# Sheet4.net
KiCad netlist of a schematic drawn in Altium Designer
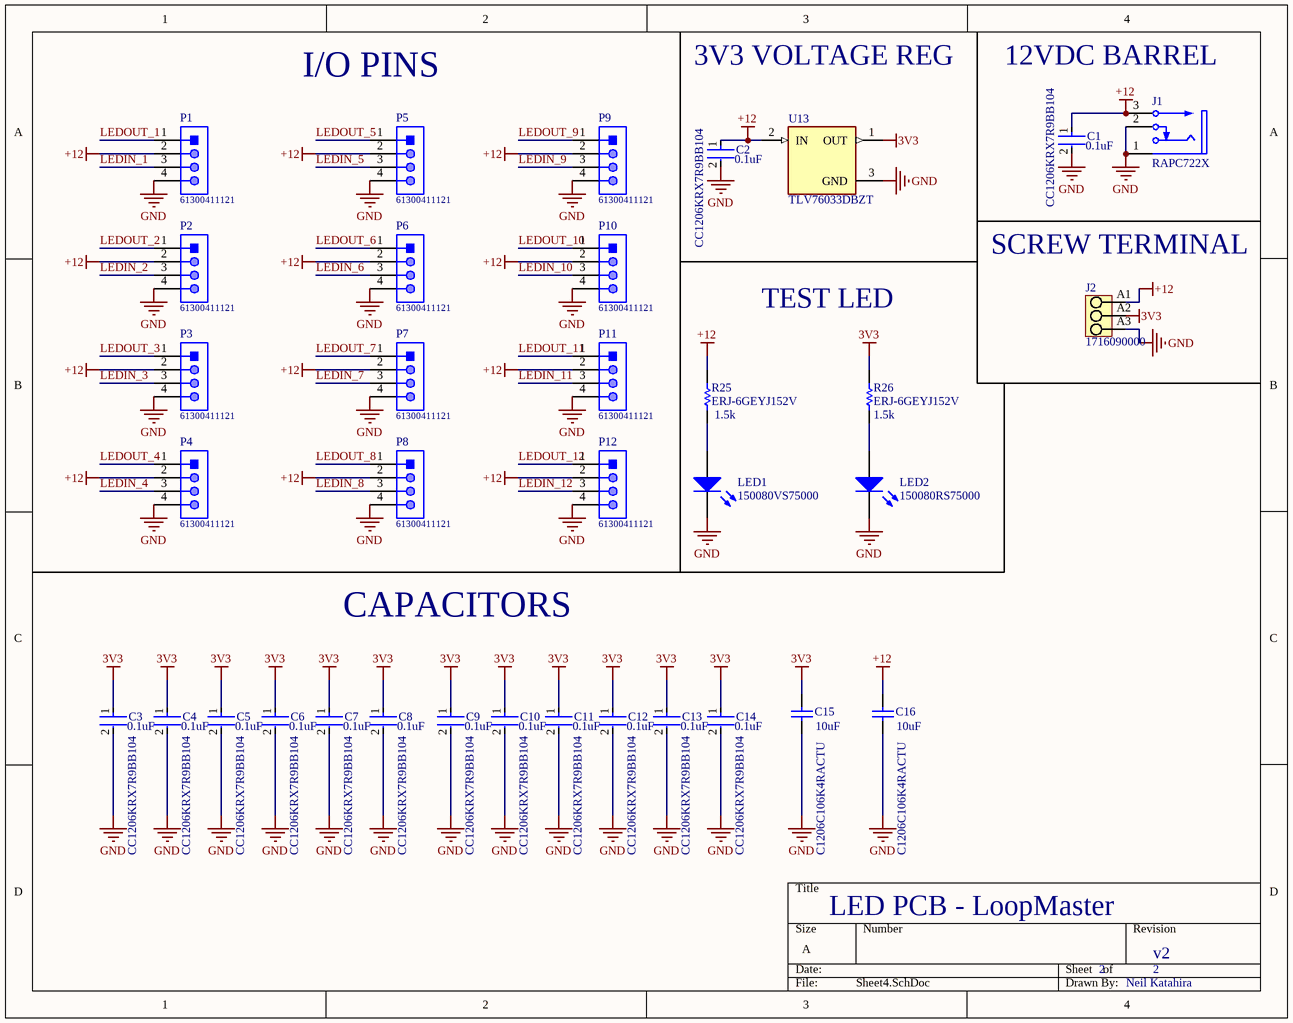
[diagram p0: Sheet4.SchDoc]

(export (version "E")
  (design (tool "Eeschema 10.0.6"))
  (components
    (comp (ref "C1")
      (value "CC1206KRX7R9BB104")
      (footprint "FP-CC1206-1_25-MFG")
      (description "CAP CER 0.1UF 50V X7R 1206")
      (fields
        (field (name "OCTOPART") "https://octopart.com/cc1206krx7r9bb104-yageo-39467816")
        (field (name "TOLERANCE") "0.1")
      )
      (libsource (lib "Altium Content Vault") (part "11868f565c42a9108669ba33697ecf6"))
    )
    (comp (ref "C2")
      (value "CC1206KRX7R9BB104")
      (footprint "FP-CC1206-1_25-MFG")
      (description "CAP CER 0.1UF 50V X7R 1206")
      (fields
        (field (name "OCTOPART") "https://octopart.com/cc1206krx7r9bb104-yageo-39467816")
        (field (name "TOLERANCE") "0.1")
      )
      (libsource (lib "Altium Content Vault") (part "11868f565c42a9108669ba33697ecf6"))
    )
    (comp (ref "C3")
      (value "CC1206KRX7R9BB104")
      (footprint "FP-CC1206-1_25-MFG")
      (description "CAP CER 0.1UF 50V X7R 1206")
      (fields
        (field (name "OCTOPART") "https://octopart.com/cc1206krx7r9bb104-yageo-39467816")
        (field (name "TOLERANCE") "0.1")
      )
      (libsource (lib "Altium Content Vault") (part "11868f565c42a9108669ba33697ecf6"))
    )
    (comp (ref "C4")
      (value "CC1206KRX7R9BB104")
      (footprint "FP-CC1206-1_25-MFG")
      (description "CAP CER 0.1UF 50V X7R 1206")
      (fields
        (field (name "OCTOPART") "https://octopart.com/cc1206krx7r9bb104-yageo-39467816")
        (field (name "TOLERANCE") "0.1")
      )
      (libsource (lib "Altium Content Vault") (part "11868f565c42a9108669ba33697ecf6"))
    )
    (comp (ref "C5")
      (value "CC1206KRX7R9BB104")
      (footprint "FP-CC1206-1_25-MFG")
      (description "CAP CER 0.1UF 50V X7R 1206")
      (fields
        (field (name "OCTOPART") "https://octopart.com/cc1206krx7r9bb104-yageo-39467816")
        (field (name "TOLERANCE") "0.1")
      )
      (libsource (lib "Altium Content Vault") (part "11868f565c42a9108669ba33697ecf6"))
    )
    (comp (ref "C6")
      (value "CC1206KRX7R9BB104")
      (footprint "FP-CC1206-1_25-MFG")
      (description "CAP CER 0.1UF 50V X7R 1206")
      (fields
        (field (name "OCTOPART") "https://octopart.com/cc1206krx7r9bb104-yageo-39467816")
        (field (name "TOLERANCE") "0.1")
      )
      (libsource (lib "Altium Content Vault") (part "11868f565c42a9108669ba33697ecf6"))
    )
    (comp (ref "C7")
      (value "CC1206KRX7R9BB104")
      (footprint "FP-CC1206-1_25-MFG")
      (description "CAP CER 0.1UF 50V X7R 1206")
      (fields
        (field (name "OCTOPART") "https://octopart.com/cc1206krx7r9bb104-yageo-39467816")
        (field (name "TOLERANCE") "0.1")
      )
      (libsource (lib "Altium Content Vault") (part "11868f565c42a9108669ba33697ecf6"))
    )
    (comp (ref "C8")
      (value "CC1206KRX7R9BB104")
      (footprint "FP-CC1206-1_25-MFG")
      (description "CAP CER 0.1UF 50V X7R 1206")
      (fields
        (field (name "OCTOPART") "https://octopart.com/cc1206krx7r9bb104-yageo-39467816")
        (field (name "TOLERANCE") "0.1")
      )
      (libsource (lib "Altium Content Vault") (part "11868f565c42a9108669ba33697ecf6"))
    )
    (comp (ref "C9")
      (value "CC1206KRX7R9BB104")
      (footprint "FP-CC1206-1_25-MFG")
      (description "CAP CER 0.1UF 50V X7R 1206")
      (fields
        (field (name "OCTOPART") "https://octopart.com/cc1206krx7r9bb104-yageo-39467816")
        (field (name "TOLERANCE") "0.1")
      )
      (libsource (lib "Altium Content Vault") (part "11868f565c42a9108669ba33697ecf6"))
    )
    (comp (ref "C10")
      (value "CC1206KRX7R9BB104")
      (footprint "FP-CC1206-1_25-MFG")
      (description "CAP CER 0.1UF 50V X7R 1206")
      (fields
        (field (name "OCTOPART") "https://octopart.com/cc1206krx7r9bb104-yageo-39467816")
        (field (name "TOLERANCE") "0.1")
      )
      (libsource (lib "Altium Content Vault") (part "11868f565c42a9108669ba33697ecf6"))
    )
    (comp (ref "C11")
      (value "CC1206KRX7R9BB104")
      (footprint "FP-CC1206-1_25-MFG")
      (description "CAP CER 0.1UF 50V X7R 1206")
      (fields
        (field (name "OCTOPART") "https://octopart.com/cc1206krx7r9bb104-yageo-39467816")
        (field (name "TOLERANCE") "0.1")
      )
      (libsource (lib "Altium Content Vault") (part "11868f565c42a9108669ba33697ecf6"))
    )
    (comp (ref "C12")
      (value "CC1206KRX7R9BB104")
      (footprint "FP-CC1206-1_25-MFG")
      (description "CAP CER 0.1UF 50V X7R 1206")
      (fields
        (field (name "OCTOPART") "https://octopart.com/cc1206krx7r9bb104-yageo-39467816")
        (field (name "TOLERANCE") "0.1")
      )
      (libsource (lib "Altium Content Vault") (part "11868f565c42a9108669ba33697ecf6"))
    )
    (comp (ref "C13")
      (value "CC1206KRX7R9BB104")
      (footprint "FP-CC1206-1_25-MFG")
      (description "CAP CER 0.1UF 50V X7R 1206")
      (fields
        (field (name "OCTOPART") "https://octopart.com/cc1206krx7r9bb104-yageo-39467816")
        (field (name "TOLERANCE") "0.1")
      )
      (libsource (lib "Altium Content Vault") (part "11868f565c42a9108669ba33697ecf6"))
    )
    (comp (ref "C14")
      (value "CC1206KRX7R9BB104")
      (footprint "FP-CC1206-1_25-MFG")
      (description "CAP CER 0.1UF 50V X7R 1206")
      (fields
        (field (name "OCTOPART") "https://octopart.com/cc1206krx7r9bb104-yageo-39467816")
        (field (name "TOLERANCE") "0.1")
      )
      (libsource (lib "Altium Content Vault") (part "11868f565c42a9108669ba33697ecf6"))
    )
    (comp (ref "C15")
      (value "C1206C106K4RACTU")
      (footprint "CAPC3216X180X50ML20T25")
      (description "CAP, Ceramic, 10 uF, +/- 10%, 16 V, -55 to 125 degC, 1206 (3216 Metric), RoHS, Tape and Reel")
      (fields (field (name "TOLERANCE") "5%"))
      (libsource (lib "Altium Content Vault") (part "CAP-NP-2"))
    )
    (comp (ref "C16")
      (value "C1206C106K4RACTU")
      (footprint "CAPC3216X180X50ML20T25")
      (description "CAP, Ceramic, 10 uF, +/- 10%, 16 V, -55 to 125 degC, 1206 (3216 Metric), RoHS, Tape and Reel")
      (fields (field (name "TOLERANCE") "5%"))
      (libsource (lib "Altium Content Vault") (part "CAP-NP-2"))
    )
    (comp (ref "J1")
      (value "RAPC722X")
      (footprint "SWITCH-RAPC712X-3_V")
      (description "Power Jack, 5 A, 3-Pin THD, RoHS, Bulk")
      (fields (field (name "MANUFACTURER") "Switchcraft"))
      (libsource (lib "Altium Content Vault") (part "SWITCH-RAPC712X-3"))
    )
    (comp (ref "J2")
      (value "1716090000")
      (footprint "LM_5_08_90_03")
      (description "OMNIMATE Signal - series LM")
      (fields (field (name "MANUFACTURER") "Weidmueller"))
      (libsource (lib "Altium Content Vault") (part "Terminal_03_1x03"))
    )
    (comp (ref "LED1")
      (value "150080VS75000")
      (footprint "0805_A")
      (description "SMD mono-color Chip LED, WL-SMCW, Bright Green")
      (fields (field (name "MANUFACTURER") "Wuerth Elektronik"))
      (libsource (lib "Altium Content Vault") (part "WE-LED_K1A2-2"))
    )
    (comp (ref "LED2")
      (value "150080RS75000")
      (footprint "0805_A")
      (description "SMD mono-color Chip LED, WL-SMCW, Red")
      (fields (field (name "MANUFACTURER") "Wuerth Elektronik"))
      (libsource (lib "Altium Content Vault") (part "WE-LED_K1A2-2"))
    )
    (comp (ref "P1")
      (value "61300411121")
      (footprint "61300411121")
      (description "THT Vertical Pin Header WR-PHD, Pitch 2.54 mm, Single Row, 4 pins")
      (fields (field (name "MANUFACTURER") "Wurth Elektronik") (field (name "PUBLISHER") "WurthElektronik"))
      (libsource (lib "Altium Content Vault") (part "WE-CN-1P-M-R4"))
    )
    (comp (ref "P2")
      (value "61300411121")
      (footprint "61300411121")
      (description "THT Vertical Pin Header WR-PHD, Pitch 2.54 mm, Single Row, 4 pins")
      (fields (field (name "MANUFACTURER") "Wurth Elektronik") (field (name "PUBLISHER") "WurthElektronik"))
      (libsource (lib "Altium Content Vault") (part "WE-CN-1P-M-R4"))
    )
    (comp (ref "P3")
      (value "61300411121")
      (footprint "61300411121")
      (description "THT Vertical Pin Header WR-PHD, Pitch 2.54 mm, Single Row, 4 pins")
      (fields (field (name "MANUFACTURER") "Wurth Elektronik") (field (name "PUBLISHER") "WurthElektronik"))
      (libsource (lib "Altium Content Vault") (part "WE-CN-1P-M-R4"))
    )
    (comp (ref "P4")
      (value "61300411121")
      (footprint "61300411121")
      (description "THT Vertical Pin Header WR-PHD, Pitch 2.54 mm, Single Row, 4 pins")
      (fields (field (name "MANUFACTURER") "Wurth Elektronik") (field (name "PUBLISHER") "WurthElektronik"))
      (libsource (lib "Altium Content Vault") (part "WE-CN-1P-M-R4"))
    )
    (comp (ref "P5")
      (value "61300411121")
      (footprint "61300411121")
      (description "THT Vertical Pin Header WR-PHD, Pitch 2.54 mm, Single Row, 4 pins")
      (fields (field (name "MANUFACTURER") "Wurth Elektronik") (field (name "PUBLISHER") "WurthElektronik"))
      (libsource (lib "Altium Content Vault") (part "WE-CN-1P-M-R4"))
    )
    (comp (ref "P6")
      (value "61300411121")
      (footprint "61300411121")
      (description "THT Vertical Pin Header WR-PHD, Pitch 2.54 mm, Single Row, 4 pins")
      (fields (field (name "MANUFACTURER") "Wurth Elektronik") (field (name "PUBLISHER") "WurthElektronik"))
      (libsource (lib "Altium Content Vault") (part "WE-CN-1P-M-R4"))
    )
    (comp (ref "P7")
      (value "61300411121")
      (footprint "61300411121")
      (description "THT Vertical Pin Header WR-PHD, Pitch 2.54 mm, Single Row, 4 pins")
      (fields (field (name "MANUFACTURER") "Wurth Elektronik") (field (name "PUBLISHER") "WurthElektronik"))
      (libsource (lib "Altium Content Vault") (part "WE-CN-1P-M-R4"))
    )
    (comp (ref "P8")
      (value "61300411121")
      (footprint "61300411121")
      (description "THT Vertical Pin Header WR-PHD, Pitch 2.54 mm, Single Row, 4 pins")
      (fields (field (name "MANUFACTURER") "Wurth Elektronik") (field (name "PUBLISHER") "WurthElektronik"))
      (libsource (lib "Altium Content Vault") (part "WE-CN-1P-M-R4"))
    )
    (comp (ref "P9")
      (value "61300411121")
      (footprint "61300411121")
      (description "THT Vertical Pin Header WR-PHD, Pitch 2.54 mm, Single Row, 4 pins")
      (fields (field (name "MANUFACTURER") "Wurth Elektronik") (field (name "PUBLISHER") "WurthElektronik"))
      (libsource (lib "Altium Content Vault") (part "WE-CN-1P-M-R4"))
    )
    (comp (ref "P10")
      (value "61300411121")
      (footprint "61300411121")
      (description "THT Vertical Pin Header WR-PHD, Pitch 2.54 mm, Single Row, 4 pins")
      (fields (field (name "MANUFACTURER") "Wurth Elektronik") (field (name "PUBLISHER") "WurthElektronik"))
      (libsource (lib "Altium Content Vault") (part "WE-CN-1P-M-R4"))
    )
    (comp (ref "P11")
      (value "61300411121")
      (footprint "61300411121")
      (description "THT Vertical Pin Header WR-PHD, Pitch 2.54 mm, Single Row, 4 pins")
      (fields (field (name "MANUFACTURER") "Wurth Elektronik") (field (name "PUBLISHER") "WurthElektronik"))
      (libsource (lib "Altium Content Vault") (part "WE-CN-1P-M-R4"))
    )
    (comp (ref "P12")
      (value "61300411121")
      (footprint "61300411121")
      (description "THT Vertical Pin Header WR-PHD, Pitch 2.54 mm, Single Row, 4 pins")
      (fields (field (name "MANUFACTURER") "Wurth Elektronik") (field (name "PUBLISHER") "WurthElektronik"))
      (libsource (lib "Altium Content Vault") (part "WE-CN-1P-M-R4"))
    )
    (comp (ref "R25")
      (value "ERJ-6GEYJ152V")
      (footprint "RESC2013X70X40NL20T20")
      (fields (field (name "MANUFACTURER") "Panasonic"))
      (libsource (lib "Altium Content Vault") (part "RES"))
    )
    (comp (ref "R26")
      (value "ERJ-6GEYJ152V")
      (footprint "RESC2013X70X40NL20T20")
      (fields (field (name "MANUFACTURER") "Panasonic"))
      (libsource (lib "Altium Content Vault") (part "RES"))
    )
    (comp (ref "U13")
      (value "TLV76033DBZT")
      (footprint "FP-DBZ0003A-MFG")
      (description "IC REG LINEAR 3.3V 100MA SOT23-3")
      (fields
        (field (name "MANUFACTURER") "Texas Instruments")
        (field (name "OCTOPART") "https://octopart.com/tlv76033dbzt-texas+instruments-84619834")
      )
      (libsource (lib "Altium Content Vault") (part "a333afa03112605246d85a120c5baff"))
    )
  )
  (nets
    (net (code "1") (name "+12") (class "Default")
      (node (ref "C1") (pin "1") (pinfunction "1_1") (pintype "passive"))
      (node (ref "C16") (pin "2") (pinfunction "2_2") (pintype "passive"))
      (node (ref "C2") (pin "1") (pinfunction "1_1") (pintype "passive"))
      (node (ref "J1") (pin "3") (pinfunction "3_3") (pintype "passive"))
      (node (ref "J2") (pin "A1") (pinfunction "A1_A1") (pintype "passive"))
      (node (ref "P1") (pin "2") (pinfunction "2_2") (pintype "passive"))
      (node (ref "P10") (pin "2") (pinfunction "2_2") (pintype "passive"))
      (node (ref "P11") (pin "2") (pinfunction "2_2") (pintype "passive"))
      (node (ref "P12") (pin "2") (pinfunction "2_2") (pintype "passive"))
      (node (ref "P2") (pin "2") (pinfunction "2_2") (pintype "passive"))
      (node (ref "P3") (pin "2") (pinfunction "2_2") (pintype "passive"))
      (node (ref "P4") (pin "2") (pinfunction "2_2") (pintype "passive"))
      (node (ref "P5") (pin "2") (pinfunction "2_2") (pintype "passive"))
      (node (ref "P6") (pin "2") (pinfunction "2_2") (pintype "passive"))
      (node (ref "P7") (pin "2") (pinfunction "2_2") (pintype "passive"))
      (node (ref "P8") (pin "2") (pinfunction "2_2") (pintype "passive"))
      (node (ref "P9") (pin "2") (pinfunction "2_2") (pintype "passive"))
      (node (ref "R25") (pin "2") (pinfunction "2_2") (pintype "passive"))
      (node (ref "U13") (pin "2") (pinfunction "IN_2") (pintype "input"))
    )
    (net (code "2") (name "/LEDIN_1") (class "Default")
      (node (ref "P1") (pin "3") (pinfunction "3_3") (pintype "passive"))
    )
    (net (code "3") (name "/LEDIN_2") (class "Default")
      (node (ref "P2") (pin "3") (pinfunction "3_3") (pintype "passive"))
    )
    (net (code "4") (name "/LEDIN_3") (class "Default")
      (node (ref "P3") (pin "3") (pinfunction "3_3") (pintype "passive"))
    )
    (net (code "5") (name "/LEDIN_4") (class "Default")
      (node (ref "P4") (pin "3") (pinfunction "3_3") (pintype "passive"))
    )
    (net (code "6") (name "/LEDIN_5") (class "Default")
      (node (ref "P5") (pin "3") (pinfunction "3_3") (pintype "passive"))
    )
    (net (code "7") (name "/LEDIN_6") (class "Default")
      (node (ref "P6") (pin "3") (pinfunction "3_3") (pintype "passive"))
    )
    (net (code "8") (name "/LEDIN_7") (class "Default")
      (node (ref "P7") (pin "3") (pinfunction "3_3") (pintype "passive"))
    )
    (net (code "9") (name "/LEDIN_8") (class "Default")
      (node (ref "P8") (pin "3") (pinfunction "3_3") (pintype "passive"))
    )
    (net (code "10") (name "/LEDIN_9") (class "Default")
      (node (ref "P9") (pin "3") (pinfunction "3_3") (pintype "passive"))
    )
    (net (code "11") (name "/LEDIN_10") (class "Default")
      (node (ref "P10") (pin "3") (pinfunction "3_3") (pintype "passive"))
    )
    (net (code "12") (name "/LEDIN_11") (class "Default")
      (node (ref "P11") (pin "3") (pinfunction "3_3") (pintype "passive"))
    )
    (net (code "13") (name "/LEDIN_12") (class "Default")
      (node (ref "P12") (pin "3") (pinfunction "3_3") (pintype "passive"))
    )
    (net (code "14") (name "/LEDOUT_1") (class "Default")
      (node (ref "P1") (pin "1") (pinfunction "1_1") (pintype "passive"))
    )
    (net (code "15") (name "/LEDOUT_2") (class "Default")
      (node (ref "P2") (pin "1") (pinfunction "1_1") (pintype "passive"))
    )
    (net (code "16") (name "/LEDOUT_3") (class "Default")
      (node (ref "P3") (pin "1") (pinfunction "1_1") (pintype "passive"))
    )
    (net (code "17") (name "/LEDOUT_4") (class "Default")
      (node (ref "P4") (pin "1") (pinfunction "1_1") (pintype "passive"))
    )
    (net (code "18") (name "/LEDOUT_5") (class "Default")
      (node (ref "P5") (pin "1") (pinfunction "1_1") (pintype "passive"))
    )
    (net (code "19") (name "/LEDOUT_6") (class "Default")
      (node (ref "P6") (pin "1") (pinfunction "1_1") (pintype "passive"))
    )
    (net (code "20") (name "/LEDOUT_7") (class "Default")
      (node (ref "P7") (pin "1") (pinfunction "1_1") (pintype "passive"))
    )
    (net (code "21") (name "/LEDOUT_8") (class "Default")
      (node (ref "P8") (pin "1") (pinfunction "1_1") (pintype "passive"))
    )
    (net (code "22") (name "/LEDOUT_9") (class "Default")
      (node (ref "P9") (pin "1") (pinfunction "1_1") (pintype "passive"))
    )
    (net (code "23") (name "/LEDOUT_10") (class "Default")
      (node (ref "P10") (pin "1") (pinfunction "1_1") (pintype "passive"))
    )
    (net (code "24") (name "/LEDOUT_11") (class "Default")
      (node (ref "P11") (pin "1") (pinfunction "1_1") (pintype "passive"))
    )
    (net (code "25") (name "/LEDOUT_12") (class "Default")
      (node (ref "P12") (pin "1") (pinfunction "1_1") (pintype "passive"))
    )
    (net (code "26") (name "3V3") (class "Default")
      (node (ref "C10") (pin "1") (pinfunction "1_1") (pintype "passive"))
      (node (ref "C11") (pin "1") (pinfunction "1_1") (pintype "passive"))
      (node (ref "C12") (pin "1") (pinfunction "1_1") (pintype "passive"))
      (node (ref "C13") (pin "1") (pinfunction "1_1") (pintype "passive"))
      (node (ref "C14") (pin "1") (pinfunction "1_1") (pintype "passive"))
      (node (ref "C15") (pin "2") (pinfunction "2_2") (pintype "passive"))
      (node (ref "C3") (pin "1") (pinfunction "1_1") (pintype "passive"))
      (node (ref "C4") (pin "1") (pinfunction "1_1") (pintype "passive"))
      (node (ref "C5") (pin "1") (pinfunction "1_1") (pintype "passive"))
      (node (ref "C6") (pin "1") (pinfunction "1_1") (pintype "passive"))
      (node (ref "C7") (pin "1") (pinfunction "1_1") (pintype "passive"))
      (node (ref "C8") (pin "1") (pinfunction "1_1") (pintype "passive"))
      (node (ref "C9") (pin "1") (pinfunction "1_1") (pintype "passive"))
      (node (ref "J2") (pin "A2") (pinfunction "A2_A2") (pintype "passive"))
      (node (ref "R26") (pin "2") (pinfunction "2_2") (pintype "passive"))
      (node (ref "U13") (pin "1") (pinfunction "OUT_1") (pintype "output"))
    )
    (net (code "27") (name "GND") (class "Default")
      (node (ref "C1") (pin "2") (pinfunction "2_2") (pintype "passive"))
      (node (ref "C10") (pin "2") (pinfunction "2_2") (pintype "passive"))
      (node (ref "C11") (pin "2") (pinfunction "2_2") (pintype "passive"))
      (node (ref "C12") (pin "2") (pinfunction "2_2") (pintype "passive"))
      (node (ref "C13") (pin "2") (pinfunction "2_2") (pintype "passive"))
      (node (ref "C14") (pin "2") (pinfunction "2_2") (pintype "passive"))
      (node (ref "C15") (pin "1") (pinfunction "1_1") (pintype "passive"))
      (node (ref "C16") (pin "1") (pinfunction "1_1") (pintype "passive"))
      (node (ref "C2") (pin "2") (pinfunction "2_2") (pintype "passive"))
      (node (ref "C3") (pin "2") (pinfunction "2_2") (pintype "passive"))
      (node (ref "C4") (pin "2") (pinfunction "2_2") (pintype "passive"))
      (node (ref "C5") (pin "2") (pinfunction "2_2") (pintype "passive"))
      (node (ref "C6") (pin "2") (pinfunction "2_2") (pintype "passive"))
      (node (ref "C7") (pin "2") (pinfunction "2_2") (pintype "passive"))
      (node (ref "C8") (pin "2") (pinfunction "2_2") (pintype "passive"))
      (node (ref "C9") (pin "2") (pinfunction "2_2") (pintype "passive"))
      (node (ref "J1") (pin "1") (pinfunction "1_1") (pintype "passive"))
      (node (ref "J1") (pin "2") (pinfunction "2_2") (pintype "passive"))
      (node (ref "J2") (pin "A3") (pinfunction "A3_A3") (pintype "passive"))
      (node (ref "LED1") (pin "1") (pinfunction "K_1") (pintype "passive"))
      (node (ref "LED2") (pin "1") (pinfunction "K_1") (pintype "passive"))
      (node (ref "P1") (pin "4") (pinfunction "4_4") (pintype "passive"))
      (node (ref "P10") (pin "4") (pinfunction "4_4") (pintype "passive"))
      (node (ref "P11") (pin "4") (pinfunction "4_4") (pintype "passive"))
      (node (ref "P12") (pin "4") (pinfunction "4_4") (pintype "passive"))
      (node (ref "P2") (pin "4") (pinfunction "4_4") (pintype "passive"))
      (node (ref "P3") (pin "4") (pinfunction "4_4") (pintype "passive"))
      (node (ref "P4") (pin "4") (pinfunction "4_4") (pintype "passive"))
      (node (ref "P5") (pin "4") (pinfunction "4_4") (pintype "passive"))
      (node (ref "P6") (pin "4") (pinfunction "4_4") (pintype "passive"))
      (node (ref "P7") (pin "4") (pinfunction "4_4") (pintype "passive"))
      (node (ref "P8") (pin "4") (pinfunction "4_4") (pintype "passive"))
      (node (ref "P9") (pin "4") (pinfunction "4_4") (pintype "passive"))
      (node (ref "U13") (pin "3") (pinfunction "GND_3") (pintype "power_in"))
    )
    (net (code "28") (name "Net-(LED1-A)") (class "Default")
      (node (ref "LED1") (pin "2") (pinfunction "A_2") (pintype "passive"))
      (node (ref "R25") (pin "1") (pinfunction "1_1") (pintype "passive"))
    )
    (net (code "29") (name "Net-(LED2-A)") (class "Default")
      (node (ref "LED2") (pin "2") (pinfunction "A_2") (pintype "passive"))
      (node (ref "R26") (pin "1") (pinfunction "1_1") (pintype "passive"))
    )
  )
)
